# keyboard.net
KiCad netlist of a schematic drawn in EAGLE
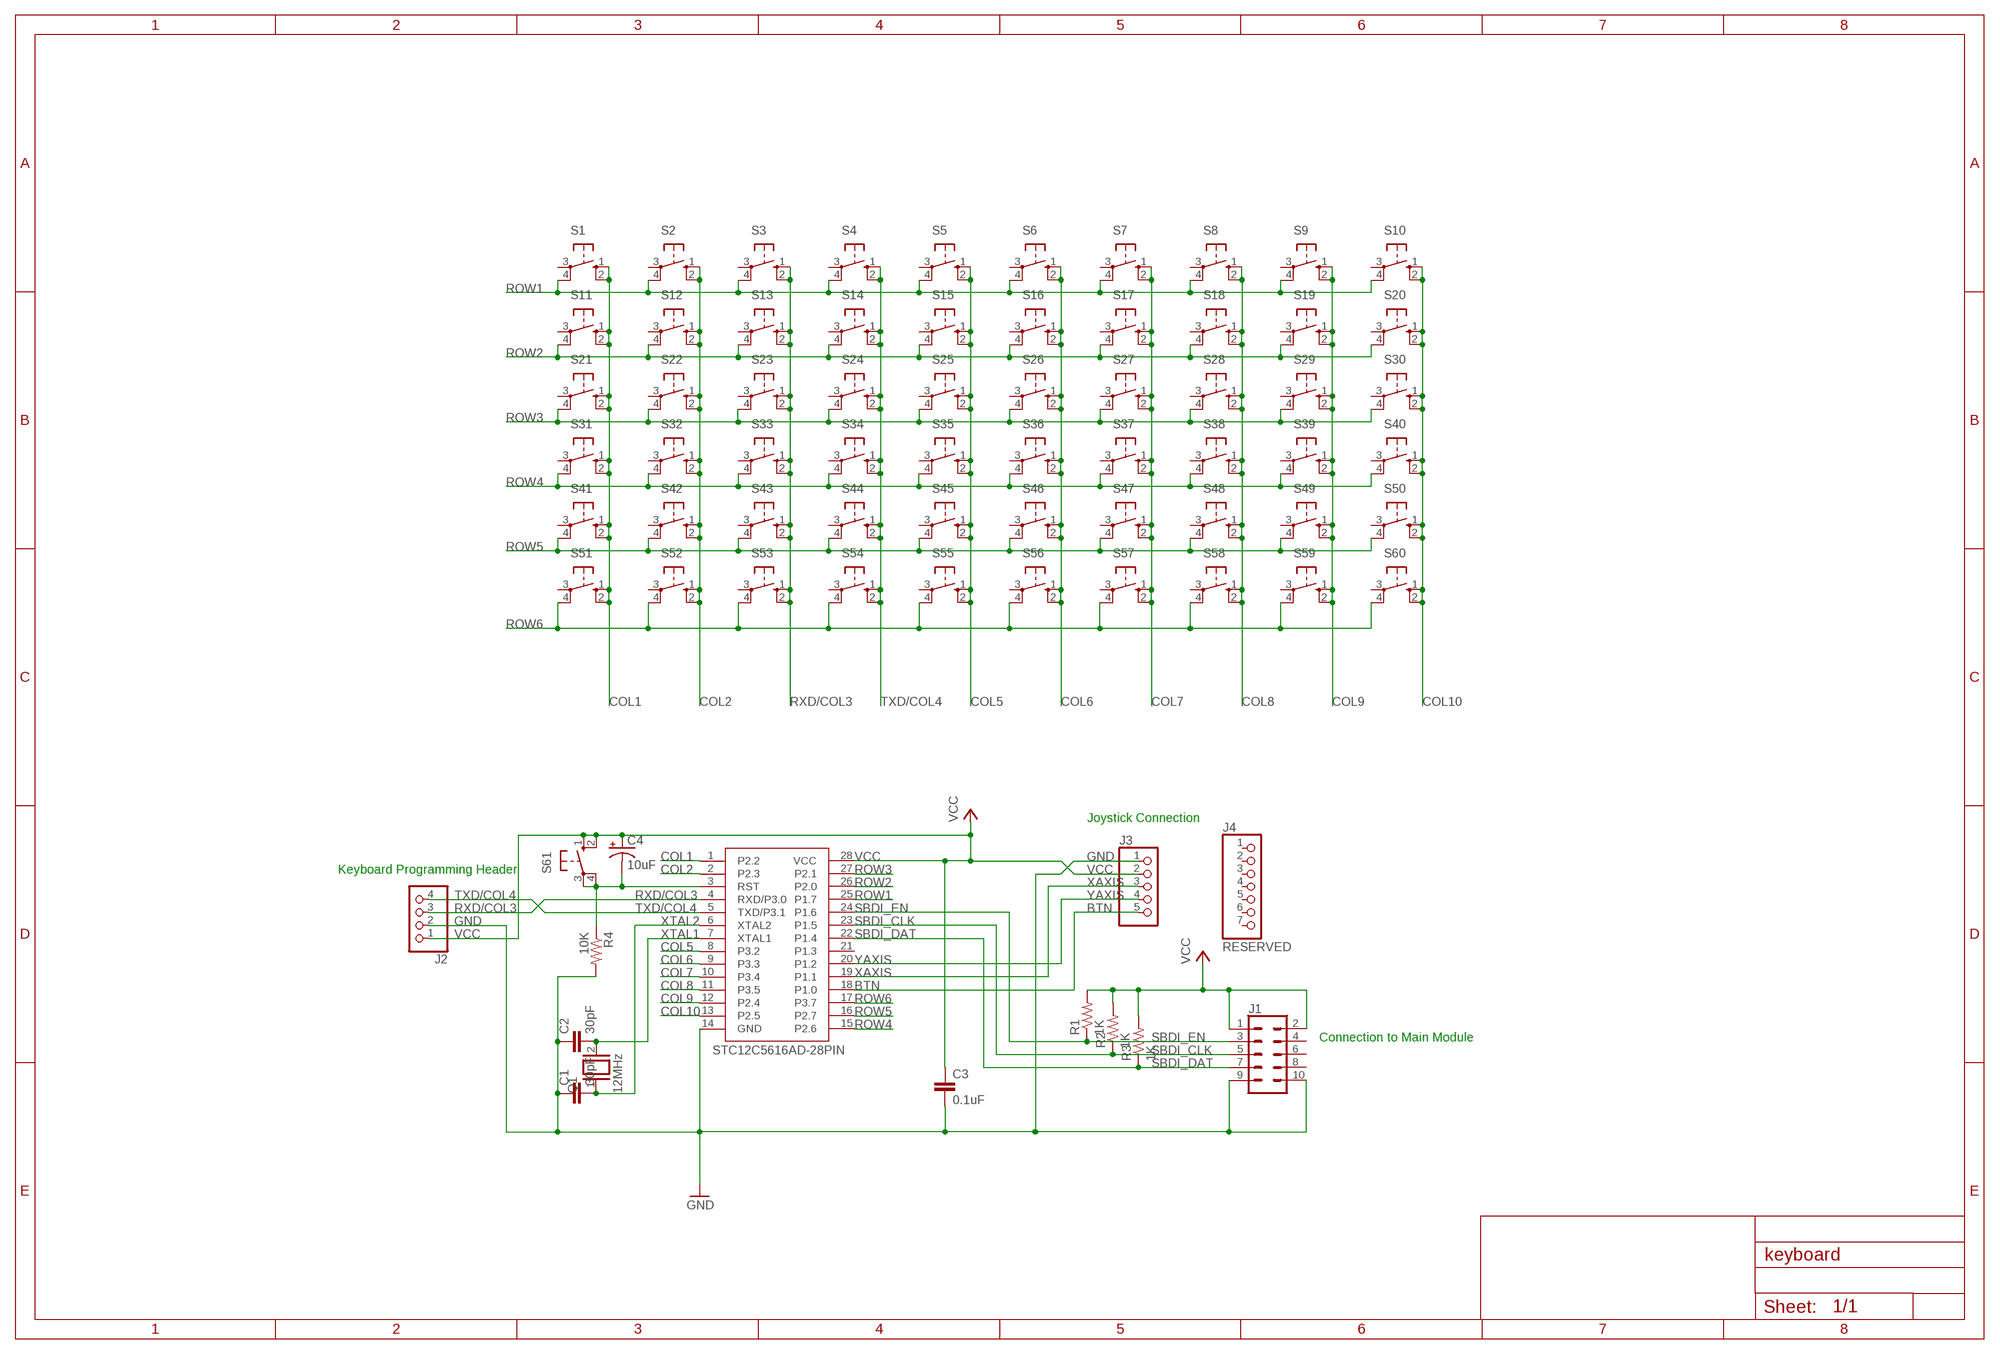
[diagram p0: schematic, sheet 1]

(export (version "E")
  (design (tool "Eeschema 10.0.6"))
  (components
    (comp (ref "C1")
      (value "30pF")
      (footprint "eagle-import:C025-025X050")
      (libsource (lib "eagle-import") (part "C-EU025-025X050"))
    )
    (comp (ref "C2")
      (value "30pF")
      (footprint "eagle-import:C025-025X050")
      (libsource (lib "eagle-import") (part "C-EU025-025X050"))
    )
    (comp (ref "C3")
      (value "0.1uF")
      (footprint "eagle-import:C025-030X050")
      (libsource (lib "eagle-import") (part "C-EU025-030X050"))
    )
    (comp (ref "C4")
      (value "10uF")
      (footprint "eagle-import:E1,8-4")
      (libsource (lib "eagle-import") (part "CPOL-USE1.8-4"))
    )
    (comp (ref "IC1")
      (value "STC12C5616AD")
      (footprint "eagle-import:DIP787W45P254L3505H508Q28B")
      (libsource (lib "eagle-import") (part "STC12C5616AD-28PIN"))
    )
    (comp (ref "J1")
      (value "CONN_05X2SHD_LOCK")
      (footprint "eagle-import:2X5-SHROUDED_LOCK")
      (libsource (lib "eagle-import") (part "CONN_05X2SHD_LOCK"))
    )
    (comp (ref "J2")
      (value "PINHD-1X4")
      (footprint "eagle-import:1X04")
      (libsource (lib "eagle-import") (part "PINHD-1X4"))
    )
    (comp (ref "J3")
      (value "PINHD-1X5")
      (footprint "eagle-import:1X05")
      (libsource (lib "eagle-import") (part "PINHD-1X5"))
    )
    (comp (ref "J4")
      (value "RESERVED")
      (footprint "eagle-import:1X07")
      (libsource (lib "eagle-import") (part "PINHD-1X7"))
    )
    (comp (ref "Q1")
      (value "12MHz")
      (footprint "eagle-import:QS")
      (libsource (lib "eagle-import") (part "XTAL/S"))
    )
    (comp (ref "R1")
      (value "1K")
      (footprint "eagle-import:0204_7")
      (libsource (lib "eagle-import") (part "R-US_0204/7"))
    )
    (comp (ref "R2")
      (value "1K")
      (footprint "eagle-import:0204_7")
      (libsource (lib "eagle-import") (part "R-US_0204/7"))
    )
    (comp (ref "R3")
      (value "1K")
      (footprint "eagle-import:0204_7")
      (libsource (lib "eagle-import") (part "R-US_0204/7"))
    )
    (comp (ref "R4")
      (value "10K")
      (footprint "eagle-import:0204_7")
      (libsource (lib "eagle-import") (part "R-US_0204/7"))
    )
    (comp (ref "S1")
      (value "10-XX")
      (footprint "eagle-import:B3F-10XX")
      (fields (field (name "MPN") "B3F-1000"))
      (libsource (lib "eagle-import") (part "10-XX"))
    )
    (comp (ref "S2")
      (value "10-XX")
      (footprint "eagle-import:B3F-10XX")
      (fields (field (name "MPN") "B3F-1000"))
      (libsource (lib "eagle-import") (part "10-XX"))
    )
    (comp (ref "S3")
      (value "10-XX")
      (footprint "eagle-import:B3F-10XX")
      (fields (field (name "MPN") "B3F-1000"))
      (libsource (lib "eagle-import") (part "10-XX"))
    )
    (comp (ref "S4")
      (value "10-XX")
      (footprint "eagle-import:B3F-10XX")
      (fields (field (name "MPN") "B3F-1000"))
      (libsource (lib "eagle-import") (part "10-XX"))
    )
    (comp (ref "S5")
      (value "10-XX")
      (footprint "eagle-import:B3F-10XX")
      (fields (field (name "MPN") "B3F-1000"))
      (libsource (lib "eagle-import") (part "10-XX"))
    )
    (comp (ref "S6")
      (value "10-XX")
      (footprint "eagle-import:B3F-10XX")
      (fields (field (name "MPN") "B3F-1000"))
      (libsource (lib "eagle-import") (part "10-XX"))
    )
    (comp (ref "S7")
      (value "10-XX")
      (footprint "eagle-import:B3F-10XX")
      (fields (field (name "MPN") "B3F-1000"))
      (libsource (lib "eagle-import") (part "10-XX"))
    )
    (comp (ref "S8")
      (value "10-XX")
      (footprint "eagle-import:B3F-10XX")
      (fields (field (name "MPN") "B3F-1000"))
      (libsource (lib "eagle-import") (part "10-XX"))
    )
    (comp (ref "S9")
      (value "10-XX")
      (footprint "eagle-import:B3F-10XX")
      (fields (field (name "MPN") "B3F-1000"))
      (libsource (lib "eagle-import") (part "10-XX"))
    )
    (comp (ref "S10")
      (value "10-XX")
      (footprint "eagle-import:B3F-10XX")
      (fields (field (name "MPN") "B3F-1000"))
      (libsource (lib "eagle-import") (part "10-XX"))
    )
    (comp (ref "S11")
      (value "10-XX")
      (footprint "eagle-import:B3F-10XX")
      (fields (field (name "MPN") "B3F-1000"))
      (libsource (lib "eagle-import") (part "10-XX"))
    )
    (comp (ref "S12")
      (value "10-XX")
      (footprint "eagle-import:B3F-10XX")
      (fields (field (name "MPN") "B3F-1000"))
      (libsource (lib "eagle-import") (part "10-XX"))
    )
    (comp (ref "S13")
      (value "10-XX")
      (footprint "eagle-import:B3F-10XX")
      (fields (field (name "MPN") "B3F-1000"))
      (libsource (lib "eagle-import") (part "10-XX"))
    )
    (comp (ref "S14")
      (value "10-XX")
      (footprint "eagle-import:B3F-10XX")
      (fields (field (name "MPN") "B3F-1000"))
      (libsource (lib "eagle-import") (part "10-XX"))
    )
    (comp (ref "S15")
      (value "10-XX")
      (footprint "eagle-import:B3F-10XX")
      (fields (field (name "MPN") "B3F-1000"))
      (libsource (lib "eagle-import") (part "10-XX"))
    )
    (comp (ref "S16")
      (value "10-XX")
      (footprint "eagle-import:B3F-10XX")
      (fields (field (name "MPN") "B3F-1000"))
      (libsource (lib "eagle-import") (part "10-XX"))
    )
    (comp (ref "S17")
      (value "10-XX")
      (footprint "eagle-import:B3F-10XX")
      (fields (field (name "MPN") "B3F-1000"))
      (libsource (lib "eagle-import") (part "10-XX"))
    )
    (comp (ref "S18")
      (value "10-XX")
      (footprint "eagle-import:B3F-10XX")
      (fields (field (name "MPN") "B3F-1000"))
      (libsource (lib "eagle-import") (part "10-XX"))
    )
    (comp (ref "S19")
      (value "10-XX")
      (footprint "eagle-import:B3F-10XX")
      (fields (field (name "MPN") "B3F-1000"))
      (libsource (lib "eagle-import") (part "10-XX"))
    )
    (comp (ref "S20")
      (value "10-XX")
      (footprint "eagle-import:B3F-10XX")
      (fields (field (name "MPN") "B3F-1000"))
      (libsource (lib "eagle-import") (part "10-XX"))
    )
    (comp (ref "S21")
      (value "10-XX")
      (footprint "eagle-import:B3F-10XX")
      (fields (field (name "MPN") "B3F-1000"))
      (libsource (lib "eagle-import") (part "10-XX"))
    )
    (comp (ref "S22")
      (value "10-XX")
      (footprint "eagle-import:B3F-10XX")
      (fields (field (name "MPN") "B3F-1000"))
      (libsource (lib "eagle-import") (part "10-XX"))
    )
    (comp (ref "S23")
      (value "10-XX")
      (footprint "eagle-import:B3F-10XX")
      (fields (field (name "MPN") "B3F-1000"))
      (libsource (lib "eagle-import") (part "10-XX"))
    )
    (comp (ref "S24")
      (value "10-XX")
      (footprint "eagle-import:B3F-10XX")
      (fields (field (name "MPN") "B3F-1000"))
      (libsource (lib "eagle-import") (part "10-XX"))
    )
    (comp (ref "S25")
      (value "10-XX")
      (footprint "eagle-import:B3F-10XX")
      (fields (field (name "MPN") "B3F-1000"))
      (libsource (lib "eagle-import") (part "10-XX"))
    )
    (comp (ref "S26")
      (value "10-XX")
      (footprint "eagle-import:B3F-10XX")
      (fields (field (name "MPN") "B3F-1000"))
      (libsource (lib "eagle-import") (part "10-XX"))
    )
    (comp (ref "S27")
      (value "10-XX")
      (footprint "eagle-import:B3F-10XX")
      (fields (field (name "MPN") "B3F-1000"))
      (libsource (lib "eagle-import") (part "10-XX"))
    )
    (comp (ref "S28")
      (value "10-XX")
      (footprint "eagle-import:B3F-10XX")
      (fields (field (name "MPN") "B3F-1000"))
      (libsource (lib "eagle-import") (part "10-XX"))
    )
    (comp (ref "S29")
      (value "10-XX")
      (footprint "eagle-import:B3F-10XX")
      (fields (field (name "MPN") "B3F-1000"))
      (libsource (lib "eagle-import") (part "10-XX"))
    )
    (comp (ref "S30")
      (value "10-XX")
      (footprint "eagle-import:B3F-10XX")
      (fields (field (name "MPN") "B3F-1000"))
      (libsource (lib "eagle-import") (part "10-XX"))
    )
    (comp (ref "S31")
      (value "10-XX")
      (footprint "eagle-import:B3F-10XX")
      (fields (field (name "MPN") "B3F-1000"))
      (libsource (lib "eagle-import") (part "10-XX"))
    )
    (comp (ref "S32")
      (value "10-XX")
      (footprint "eagle-import:B3F-10XX")
      (fields (field (name "MPN") "B3F-1000"))
      (libsource (lib "eagle-import") (part "10-XX"))
    )
    (comp (ref "S33")
      (value "10-XX")
      (footprint "eagle-import:B3F-10XX")
      (fields (field (name "MPN") "B3F-1000"))
      (libsource (lib "eagle-import") (part "10-XX"))
    )
    (comp (ref "S34")
      (value "10-XX")
      (footprint "eagle-import:B3F-10XX")
      (fields (field (name "MPN") "B3F-1000"))
      (libsource (lib "eagle-import") (part "10-XX"))
    )
    (comp (ref "S35")
      (value "10-XX")
      (footprint "eagle-import:B3F-10XX")
      (fields (field (name "MPN") "B3F-1000"))
      (libsource (lib "eagle-import") (part "10-XX"))
    )
    (comp (ref "S36")
      (value "10-XX")
      (footprint "eagle-import:B3F-10XX")
      (fields (field (name "MPN") "B3F-1000"))
      (libsource (lib "eagle-import") (part "10-XX"))
    )
    (comp (ref "S37")
      (value "10-XX")
      (footprint "eagle-import:B3F-10XX")
      (fields (field (name "MPN") "B3F-1000"))
      (libsource (lib "eagle-import") (part "10-XX"))
    )
    (comp (ref "S38")
      (value "10-XX")
      (footprint "eagle-import:B3F-10XX")
      (fields (field (name "MPN") "B3F-1000"))
      (libsource (lib "eagle-import") (part "10-XX"))
    )
    (comp (ref "S39")
      (value "10-XX")
      (footprint "eagle-import:B3F-10XX")
      (fields (field (name "MPN") "B3F-1000"))
      (libsource (lib "eagle-import") (part "10-XX"))
    )
    (comp (ref "S40")
      (value "10-XX")
      (footprint "eagle-import:B3F-10XX")
      (fields (field (name "MPN") "B3F-1000"))
      (libsource (lib "eagle-import") (part "10-XX"))
    )
    (comp (ref "S41")
      (value "10-XX")
      (footprint "eagle-import:B3F-10XX")
      (fields (field (name "MPN") "B3F-1000"))
      (libsource (lib "eagle-import") (part "10-XX"))
    )
    (comp (ref "S42")
      (value "10-XX")
      (footprint "eagle-import:B3F-10XX")
      (fields (field (name "MPN") "B3F-1000"))
      (libsource (lib "eagle-import") (part "10-XX"))
    )
    (comp (ref "S43")
      (value "10-XX")
      (footprint "eagle-import:B3F-10XX")
      (fields (field (name "MPN") "B3F-1000"))
      (libsource (lib "eagle-import") (part "10-XX"))
    )
    (comp (ref "S44")
      (value "10-XX")
      (footprint "eagle-import:B3F-10XX")
      (fields (field (name "MPN") "B3F-1000"))
      (libsource (lib "eagle-import") (part "10-XX"))
    )
    (comp (ref "S45")
      (value "10-XX")
      (footprint "eagle-import:B3F-10XX")
      (fields (field (name "MPN") "B3F-1000"))
      (libsource (lib "eagle-import") (part "10-XX"))
    )
    (comp (ref "S46")
      (value "10-XX")
      (footprint "eagle-import:B3F-10XX")
      (fields (field (name "MPN") "B3F-1000"))
      (libsource (lib "eagle-import") (part "10-XX"))
    )
    (comp (ref "S47")
      (value "10-XX")
      (footprint "eagle-import:B3F-10XX")
      (fields (field (name "MPN") "B3F-1000"))
      (libsource (lib "eagle-import") (part "10-XX"))
    )
    (comp (ref "S48")
      (value "10-XX")
      (footprint "eagle-import:B3F-10XX")
      (fields (field (name "MPN") "B3F-1000"))
      (libsource (lib "eagle-import") (part "10-XX"))
    )
    (comp (ref "S49")
      (value "10-XX")
      (footprint "eagle-import:B3F-10XX")
      (fields (field (name "MPN") "B3F-1000"))
      (libsource (lib "eagle-import") (part "10-XX"))
    )
    (comp (ref "S50")
      (value "10-XX")
      (footprint "eagle-import:B3F-10XX")
      (fields (field (name "MPN") "B3F-1000"))
      (libsource (lib "eagle-import") (part "10-XX"))
    )
    (comp (ref "S51")
      (value "10-XX")
      (footprint "eagle-import:B3F-10XX")
      (fields (field (name "MPN") "B3F-1000"))
      (libsource (lib "eagle-import") (part "10-XX"))
    )
    (comp (ref "S52")
      (value "10-XX")
      (footprint "eagle-import:B3F-10XX")
      (fields (field (name "MPN") "B3F-1000"))
      (libsource (lib "eagle-import") (part "10-XX"))
    )
    (comp (ref "S53")
      (value "10-XX")
      (footprint "eagle-import:B3F-10XX")
      (fields (field (name "MPN") "B3F-1000"))
      (libsource (lib "eagle-import") (part "10-XX"))
    )
    (comp (ref "S54")
      (value "10-XX")
      (footprint "eagle-import:B3F-10XX")
      (fields (field (name "MPN") "B3F-1000"))
      (libsource (lib "eagle-import") (part "10-XX"))
    )
    (comp (ref "S55")
      (value "10-XX")
      (footprint "eagle-import:B3F-10XX")
      (fields (field (name "MPN") "B3F-1000"))
      (libsource (lib "eagle-import") (part "10-XX"))
    )
    (comp (ref "S56")
      (value "10-XX")
      (footprint "eagle-import:B3F-10XX")
      (fields (field (name "MPN") "B3F-1000"))
      (libsource (lib "eagle-import") (part "10-XX"))
    )
    (comp (ref "S57")
      (value "10-XX")
      (footprint "eagle-import:B3F-10XX")
      (fields (field (name "MPN") "B3F-1000"))
      (libsource (lib "eagle-import") (part "10-XX"))
    )
    (comp (ref "S58")
      (value "10-XX")
      (footprint "eagle-import:B3F-10XX")
      (fields (field (name "MPN") "B3F-1000"))
      (libsource (lib "eagle-import") (part "10-XX"))
    )
    (comp (ref "S59")
      (value "10-XX")
      (footprint "eagle-import:B3F-10XX")
      (fields (field (name "MPN") "B3F-1000"))
      (libsource (lib "eagle-import") (part "10-XX"))
    )
    (comp (ref "S60")
      (value "10-XX")
      (footprint "eagle-import:B3F-10XX")
      (fields (field (name "MPN") "B3F-1000"))
      (libsource (lib "eagle-import") (part "10-XX"))
    )
    (comp (ref "S61")
      (value "10-XX")
      (footprint "eagle-import:B3F-10XX")
      (fields (field (name "MPN") "B3F-1000"))
      (libsource (lib "eagle-import") (part "10-XX"))
    )
  )
  (nets
    (net (code "1") (name "/BTN") (class "Default")
      (node (ref "IC1") (pin "18") (pinfunction "P1.0_18") (pintype "bidirectional"))
      (node (ref "J3") (pin "5") (pinfunction "5_5") (pintype "passive"))
    )
    (net (code "2") (name "/COL1") (class "Default")
      (node (ref "IC1") (pin "1") (pinfunction "P2.2_1") (pintype "bidirectional"))
      (node (ref "S1") (pin "1") (pinfunction "S_1") (pintype "passive"))
      (node (ref "S1") (pin "2") (pinfunction "S1_2") (pintype "passive"))
      (node (ref "S11") (pin "1") (pinfunction "S_1") (pintype "passive"))
      (node (ref "S11") (pin "2") (pinfunction "S1_2") (pintype "passive"))
      (node (ref "S21") (pin "1") (pinfunction "S_1") (pintype "passive"))
      (node (ref "S21") (pin "2") (pinfunction "S1_2") (pintype "passive"))
      (node (ref "S31") (pin "1") (pinfunction "S_1") (pintype "passive"))
      (node (ref "S31") (pin "2") (pinfunction "S1_2") (pintype "passive"))
      (node (ref "S41") (pin "1") (pinfunction "S_1") (pintype "passive"))
      (node (ref "S41") (pin "2") (pinfunction "S1_2") (pintype "passive"))
      (node (ref "S51") (pin "1") (pinfunction "S_1") (pintype "passive"))
      (node (ref "S51") (pin "2") (pinfunction "S1_2") (pintype "passive"))
    )
    (net (code "3") (name "/COL2") (class "Default")
      (node (ref "IC1") (pin "2") (pinfunction "P2.3_2") (pintype "bidirectional"))
      (node (ref "S12") (pin "1") (pinfunction "S_1") (pintype "passive"))
      (node (ref "S12") (pin "2") (pinfunction "S1_2") (pintype "passive"))
      (node (ref "S2") (pin "1") (pinfunction "S_1") (pintype "passive"))
      (node (ref "S2") (pin "2") (pinfunction "S1_2") (pintype "passive"))
      (node (ref "S22") (pin "1") (pinfunction "S_1") (pintype "passive"))
      (node (ref "S22") (pin "2") (pinfunction "S1_2") (pintype "passive"))
      (node (ref "S32") (pin "1") (pinfunction "S_1") (pintype "passive"))
      (node (ref "S32") (pin "2") (pinfunction "S1_2") (pintype "passive"))
      (node (ref "S42") (pin "1") (pinfunction "S_1") (pintype "passive"))
      (node (ref "S42") (pin "2") (pinfunction "S1_2") (pintype "passive"))
      (node (ref "S52") (pin "1") (pinfunction "S_1") (pintype "passive"))
      (node (ref "S52") (pin "2") (pinfunction "S1_2") (pintype "passive"))
    )
    (net (code "4") (name "/COL5") (class "Default")
      (node (ref "IC1") (pin "8") (pinfunction "P3.2_8") (pintype "bidirectional"))
      (node (ref "S15") (pin "1") (pinfunction "S_1") (pintype "passive"))
      (node (ref "S15") (pin "2") (pinfunction "S1_2") (pintype "passive"))
      (node (ref "S25") (pin "1") (pinfunction "S_1") (pintype "passive"))
      (node (ref "S25") (pin "2") (pinfunction "S1_2") (pintype "passive"))
      (node (ref "S35") (pin "1") (pinfunction "S_1") (pintype "passive"))
      (node (ref "S35") (pin "2") (pinfunction "S1_2") (pintype "passive"))
      (node (ref "S45") (pin "1") (pinfunction "S_1") (pintype "passive"))
      (node (ref "S45") (pin "2") (pinfunction "S1_2") (pintype "passive"))
      (node (ref "S5") (pin "1") (pinfunction "S_1") (pintype "passive"))
      (node (ref "S5") (pin "2") (pinfunction "S1_2") (pintype "passive"))
      (node (ref "S55") (pin "1") (pinfunction "S_1") (pintype "passive"))
      (node (ref "S55") (pin "2") (pinfunction "S1_2") (pintype "passive"))
    )
    (net (code "5") (name "/COL6") (class "Default")
      (node (ref "IC1") (pin "9") (pinfunction "P3.3_9") (pintype "bidirectional"))
      (node (ref "S16") (pin "1") (pinfunction "S_1") (pintype "passive"))
      (node (ref "S16") (pin "2") (pinfunction "S1_2") (pintype "passive"))
      (node (ref "S26") (pin "1") (pinfunction "S_1") (pintype "passive"))
      (node (ref "S26") (pin "2") (pinfunction "S1_2") (pintype "passive"))
      (node (ref "S36") (pin "1") (pinfunction "S_1") (pintype "passive"))
      (node (ref "S36") (pin "2") (pinfunction "S1_2") (pintype "passive"))
      (node (ref "S46") (pin "1") (pinfunction "S_1") (pintype "passive"))
      (node (ref "S46") (pin "2") (pinfunction "S1_2") (pintype "passive"))
      (node (ref "S56") (pin "1") (pinfunction "S_1") (pintype "passive"))
      (node (ref "S56") (pin "2") (pinfunction "S1_2") (pintype "passive"))
      (node (ref "S6") (pin "1") (pinfunction "S_1") (pintype "passive"))
      (node (ref "S6") (pin "2") (pinfunction "S1_2") (pintype "passive"))
    )
    (net (code "6") (name "/COL7") (class "Default")
      (node (ref "IC1") (pin "10") (pinfunction "P3.4_10") (pintype "bidirectional"))
      (node (ref "S17") (pin "1") (pinfunction "S_1") (pintype "passive"))
      (node (ref "S17") (pin "2") (pinfunction "S1_2") (pintype "passive"))
      (node (ref "S27") (pin "1") (pinfunction "S_1") (pintype "passive"))
      (node (ref "S27") (pin "2") (pinfunction "S1_2") (pintype "passive"))
      (node (ref "S37") (pin "1") (pinfunction "S_1") (pintype "passive"))
      (node (ref "S37") (pin "2") (pinfunction "S1_2") (pintype "passive"))
      (node (ref "S47") (pin "1") (pinfunction "S_1") (pintype "passive"))
      (node (ref "S47") (pin "2") (pinfunction "S1_2") (pintype "passive"))
      (node (ref "S57") (pin "1") (pinfunction "S_1") (pintype "passive"))
      (node (ref "S57") (pin "2") (pinfunction "S1_2") (pintype "passive"))
      (node (ref "S7") (pin "1") (pinfunction "S_1") (pintype "passive"))
      (node (ref "S7") (pin "2") (pinfunction "S1_2") (pintype "passive"))
    )
    (net (code "7") (name "/COL8") (class "Default")
      (node (ref "IC1") (pin "11") (pinfunction "P3.5_11") (pintype "bidirectional"))
      (node (ref "S18") (pin "1") (pinfunction "S_1") (pintype "passive"))
      (node (ref "S18") (pin "2") (pinfunction "S1_2") (pintype "passive"))
      (node (ref "S28") (pin "1") (pinfunction "S_1") (pintype "passive"))
      (node (ref "S28") (pin "2") (pinfunction "S1_2") (pintype "passive"))
      (node (ref "S38") (pin "1") (pinfunction "S_1") (pintype "passive"))
      (node (ref "S38") (pin "2") (pinfunction "S1_2") (pintype "passive"))
      (node (ref "S48") (pin "1") (pinfunction "S_1") (pintype "passive"))
      (node (ref "S48") (pin "2") (pinfunction "S1_2") (pintype "passive"))
      (node (ref "S58") (pin "1") (pinfunction "S_1") (pintype "passive"))
      (node (ref "S58") (pin "2") (pinfunction "S1_2") (pintype "passive"))
      (node (ref "S8") (pin "1") (pinfunction "S_1") (pintype "passive"))
      (node (ref "S8") (pin "2") (pinfunction "S1_2") (pintype "passive"))
    )
    (net (code "8") (name "/COL9") (class "Default")
      (node (ref "IC1") (pin "12") (pinfunction "P2.4_12") (pintype "bidirectional"))
      (node (ref "S19") (pin "1") (pinfunction "S_1") (pintype "passive"))
      (node (ref "S19") (pin "2") (pinfunction "S1_2") (pintype "passive"))
      (node (ref "S29") (pin "1") (pinfunction "S_1") (pintype "passive"))
      (node (ref "S29") (pin "2") (pinfunction "S1_2") (pintype "passive"))
      (node (ref "S39") (pin "1") (pinfunction "S_1") (pintype "passive"))
      (node (ref "S39") (pin "2") (pinfunction "S1_2") (pintype "passive"))
      (node (ref "S49") (pin "1") (pinfunction "S_1") (pintype "passive"))
      (node (ref "S49") (pin "2") (pinfunction "S1_2") (pintype "passive"))
      (node (ref "S59") (pin "1") (pinfunction "S_1") (pintype "passive"))
      (node (ref "S59") (pin "2") (pinfunction "S1_2") (pintype "passive"))
      (node (ref "S9") (pin "1") (pinfunction "S_1") (pintype "passive"))
      (node (ref "S9") (pin "2") (pinfunction "S1_2") (pintype "passive"))
    )
    (net (code "9") (name "/COL10") (class "Default")
      (node (ref "IC1") (pin "13") (pinfunction "P2.5_13") (pintype "bidirectional"))
      (node (ref "S10") (pin "1") (pinfunction "S_1") (pintype "passive"))
      (node (ref "S10") (pin "2") (pinfunction "S1_2") (pintype "passive"))
      (node (ref "S20") (pin "1") (pinfunction "S_1") (pintype "passive"))
      (node (ref "S20") (pin "2") (pinfunction "S1_2") (pintype "passive"))
      (node (ref "S30") (pin "1") (pinfunction "S_1") (pintype "passive"))
      (node (ref "S30") (pin "2") (pinfunction "S1_2") (pintype "passive"))
      (node (ref "S40") (pin "1") (pinfunction "S_1") (pintype "passive"))
      (node (ref "S40") (pin "2") (pinfunction "S1_2") (pintype "passive"))
      (node (ref "S50") (pin "1") (pinfunction "S_1") (pintype "passive"))
      (node (ref "S50") (pin "2") (pinfunction "S1_2") (pintype "passive"))
      (node (ref "S60") (pin "1") (pinfunction "S_1") (pintype "passive"))
      (node (ref "S60") (pin "2") (pinfunction "S1_2") (pintype "passive"))
    )
    (net (code "10") (name "/ROW1") (class "Default")
      (node (ref "IC1") (pin "25") (pinfunction "P1.7_25") (pintype "bidirectional"))
      (node (ref "S1") (pin "4") (pinfunction "P1_4") (pintype "passive"))
      (node (ref "S10") (pin "4") (pinfunction "P1_4") (pintype "passive"))
      (node (ref "S2") (pin "4") (pinfunction "P1_4") (pintype "passive"))
      (node (ref "S3") (pin "4") (pinfunction "P1_4") (pintype "passive"))
      (node (ref "S4") (pin "4") (pinfunction "P1_4") (pintype "passive"))
      (node (ref "S5") (pin "4") (pinfunction "P1_4") (pintype "passive"))
      (node (ref "S6") (pin "4") (pinfunction "P1_4") (pintype "passive"))
      (node (ref "S7") (pin "4") (pinfunction "P1_4") (pintype "passive"))
      (node (ref "S8") (pin "4") (pinfunction "P1_4") (pintype "passive"))
      (node (ref "S9") (pin "4") (pinfunction "P1_4") (pintype "passive"))
    )
    (net (code "11") (name "/ROW2") (class "Default")
      (node (ref "IC1") (pin "26") (pinfunction "P2.0_26") (pintype "bidirectional"))
      (node (ref "S11") (pin "4") (pinfunction "P1_4") (pintype "passive"))
      (node (ref "S12") (pin "4") (pinfunction "P1_4") (pintype "passive"))
      (node (ref "S13") (pin "4") (pinfunction "P1_4") (pintype "passive"))
      (node (ref "S14") (pin "4") (pinfunction "P1_4") (pintype "passive"))
      (node (ref "S15") (pin "4") (pinfunction "P1_4") (pintype "passive"))
      (node (ref "S16") (pin "4") (pinfunction "P1_4") (pintype "passive"))
      (node (ref "S17") (pin "4") (pinfunction "P1_4") (pintype "passive"))
      (node (ref "S18") (pin "4") (pinfunction "P1_4") (pintype "passive"))
      (node (ref "S19") (pin "4") (pinfunction "P1_4") (pintype "passive"))
      (node (ref "S20") (pin "4") (pinfunction "P1_4") (pintype "passive"))
    )
    (net (code "12") (name "/ROW3") (class "Default")
      (node (ref "IC1") (pin "27") (pinfunction "P2.1_27") (pintype "bidirectional"))
      (node (ref "S21") (pin "4") (pinfunction "P1_4") (pintype "passive"))
      (node (ref "S22") (pin "4") (pinfunction "P1_4") (pintype "passive"))
      (node (ref "S23") (pin "4") (pinfunction "P1_4") (pintype "passive"))
      (node (ref "S24") (pin "4") (pinfunction "P1_4") (pintype "passive"))
      (node (ref "S25") (pin "4") (pinfunction "P1_4") (pintype "passive"))
      (node (ref "S26") (pin "4") (pinfunction "P1_4") (pintype "passive"))
      (node (ref "S27") (pin "4") (pinfunction "P1_4") (pintype "passive"))
      (node (ref "S28") (pin "4") (pinfunction "P1_4") (pintype "passive"))
      (node (ref "S29") (pin "4") (pinfunction "P1_4") (pintype "passive"))
      (node (ref "S30") (pin "4") (pinfunction "P1_4") (pintype "passive"))
    )
    (net (code "13") (name "/ROW4") (class "Default")
      (node (ref "IC1") (pin "15") (pinfunction "P2.6_15") (pintype "bidirectional"))
      (node (ref "S31") (pin "4") (pinfunction "P1_4") (pintype "passive"))
      (node (ref "S32") (pin "4") (pinfunction "P1_4") (pintype "passive"))
      (node (ref "S33") (pin "4") (pinfunction "P1_4") (pintype "passive"))
      (node (ref "S34") (pin "4") (pinfunction "P1_4") (pintype "passive"))
      (node (ref "S35") (pin "4") (pinfunction "P1_4") (pintype "passive"))
      (node (ref "S36") (pin "4") (pinfunction "P1_4") (pintype "passive"))
      (node (ref "S37") (pin "4") (pinfunction "P1_4") (pintype "passive"))
      (node (ref "S38") (pin "4") (pinfunction "P1_4") (pintype "passive"))
      (node (ref "S39") (pin "4") (pinfunction "P1_4") (pintype "passive"))
      (node (ref "S40") (pin "4") (pinfunction "P1_4") (pintype "passive"))
    )
    (net (code "14") (name "/ROW5") (class "Default")
      (node (ref "IC1") (pin "16") (pinfunction "P2.7_16") (pintype "bidirectional"))
      (node (ref "S41") (pin "4") (pinfunction "P1_4") (pintype "passive"))
      (node (ref "S42") (pin "4") (pinfunction "P1_4") (pintype "passive"))
      (node (ref "S43") (pin "4") (pinfunction "P1_4") (pintype "passive"))
      (node (ref "S44") (pin "4") (pinfunction "P1_4") (pintype "passive"))
      (node (ref "S45") (pin "4") (pinfunction "P1_4") (pintype "passive"))
      (node (ref "S46") (pin "4") (pinfunction "P1_4") (pintype "passive"))
      (node (ref "S47") (pin "4") (pinfunction "P1_4") (pintype "passive"))
      (node (ref "S48") (pin "4") (pinfunction "P1_4") (pintype "passive"))
      (node (ref "S49") (pin "4") (pinfunction "P1_4") (pintype "passive"))
      (node (ref "S50") (pin "4") (pinfunction "P1_4") (pintype "passive"))
    )
    (net (code "15") (name "/ROW6") (class "Default")
      (node (ref "IC1") (pin "17") (pinfunction "P3.7_17") (pintype "bidirectional"))
      (node (ref "S51") (pin "4") (pinfunction "P1_4") (pintype "passive"))
      (node (ref "S52") (pin "4") (pinfunction "P1_4") (pintype "passive"))
      (node (ref "S53") (pin "4") (pinfunction "P1_4") (pintype "passive"))
      (node (ref "S54") (pin "4") (pinfunction "P1_4") (pintype "passive"))
      (node (ref "S55") (pin "4") (pinfunction "P1_4") (pintype "passive"))
      (node (ref "S56") (pin "4") (pinfunction "P1_4") (pintype "passive"))
      (node (ref "S57") (pin "4") (pinfunction "P1_4") (pintype "passive"))
      (node (ref "S58") (pin "4") (pinfunction "P1_4") (pintype "passive"))
      (node (ref "S59") (pin "4") (pinfunction "P1_4") (pintype "passive"))
      (node (ref "S60") (pin "4") (pinfunction "P1_4") (pintype "passive"))
    )
    (net (code "16") (name "/RXD{slash}COL3") (class "Default")
      (node (ref "IC1") (pin "4") (pinfunction "RXD/P3.0_4") (pintype "bidirectional"))
      (node (ref "J2") (pin "3") (pinfunction "3_3") (pintype "passive"))
      (node (ref "S13") (pin "1") (pinfunction "S_1") (pintype "passive"))
      (node (ref "S13") (pin "2") (pinfunction "S1_2") (pintype "passive"))
      (node (ref "S23") (pin "1") (pinfunction "S_1") (pintype "passive"))
      (node (ref "S23") (pin "2") (pinfunction "S1_2") (pintype "passive"))
      (node (ref "S3") (pin "1") (pinfunction "S_1") (pintype "passive"))
      (node (ref "S3") (pin "2") (pinfunction "S1_2") (pintype "passive"))
      (node (ref "S33") (pin "1") (pinfunction "S_1") (pintype "passive"))
      (node (ref "S33") (pin "2") (pinfunction "S1_2") (pintype "passive"))
      (node (ref "S43") (pin "1") (pinfunction "S_1") (pintype "passive"))
      (node (ref "S43") (pin "2") (pinfunction "S1_2") (pintype "passive"))
      (node (ref "S53") (pin "1") (pinfunction "S_1") (pintype "passive"))
      (node (ref "S53") (pin "2") (pinfunction "S1_2") (pintype "passive"))
    )
    (net (code "17") (name "/SBDI_CLK") (class "Default")
      (node (ref "IC1") (pin "23") (pinfunction "P1.5_23") (pintype "bidirectional"))
      (node (ref "J1") (pin "5") (pinfunction "5_5") (pintype "passive"))
      (node (ref "R2") (pin "1") (pinfunction "1_1") (pintype "passive"))
    )
    (net (code "18") (name "/SBDI_DAT") (class "Default")
      (node (ref "IC1") (pin "22") (pinfunction "P1.4_22") (pintype "bidirectional"))
      (node (ref "J1") (pin "7") (pinfunction "7_7") (pintype "passive"))
      (node (ref "R3") (pin "1") (pinfunction "1_1") (pintype "passive"))
    )
    (net (code "19") (name "/SBDI_EN") (class "Default")
      (node (ref "IC1") (pin "24") (pinfunction "P1.6_24") (pintype "bidirectional"))
      (node (ref "J1") (pin "3") (pinfunction "3_3") (pintype "passive"))
      (node (ref "R1") (pin "1") (pinfunction "1_1") (pintype "passive"))
    )
    (net (code "20") (name "/TXD{slash}COL4") (class "Default")
      (node (ref "IC1") (pin "5") (pinfunction "TXD/P3.1_5") (pintype "bidirectional"))
      (node (ref "J2") (pin "4") (pinfunction "4_4") (pintype "passive"))
      (node (ref "S14") (pin "1") (pinfunction "S_1") (pintype "passive"))
      (node (ref "S14") (pin "2") (pinfunction "S1_2") (pintype "passive"))
      (node (ref "S24") (pin "1") (pinfunction "S_1") (pintype "passive"))
      (node (ref "S24") (pin "2") (pinfunction "S1_2") (pintype "passive"))
      (node (ref "S34") (pin "1") (pinfunction "S_1") (pintype "passive"))
      (node (ref "S34") (pin "2") (pinfunction "S1_2") (pintype "passive"))
      (node (ref "S4") (pin "1") (pinfunction "S_1") (pintype "passive"))
      (node (ref "S4") (pin "2") (pinfunction "S1_2") (pintype "passive"))
      (node (ref "S44") (pin "1") (pinfunction "S_1") (pintype "passive"))
      (node (ref "S44") (pin "2") (pinfunction "S1_2") (pintype "passive"))
      (node (ref "S54") (pin "1") (pinfunction "S_1") (pintype "passive"))
      (node (ref "S54") (pin "2") (pinfunction "S1_2") (pintype "passive"))
    )
    (net (code "21") (name "/XAXIS") (class "Default")
      (node (ref "IC1") (pin "19") (pinfunction "P1.1_19") (pintype "bidirectional"))
      (node (ref "J3") (pin "3") (pinfunction "3_3") (pintype "passive"))
    )
    (net (code "22") (name "/XTAL1") (class "Default")
      (node (ref "C2") (pin "2") (pinfunction "2_2") (pintype "passive"))
      (node (ref "IC1") (pin "7") (pinfunction "XTAL1_7") (pintype "bidirectional"))
      (node (ref "Q1") (pin "2") (pinfunction "2_2") (pintype "passive"))
    )
    (net (code "23") (name "/XTAL2") (class "Default")
      (node (ref "C1") (pin "2") (pinfunction "2_2") (pintype "passive"))
      (node (ref "IC1") (pin "6") (pinfunction "XTAL2_6") (pintype "bidirectional"))
      (node (ref "Q1") (pin "1") (pinfunction "1_1") (pintype "passive"))
    )
    (net (code "24") (name "/YAXIS") (class "Default")
      (node (ref "IC1") (pin "20") (pinfunction "P1.2_20") (pintype "bidirectional"))
      (node (ref "J3") (pin "4") (pinfunction "4_4") (pintype "passive"))
    )
    (net (code "25") (name "GND") (class "Default")
      (node (ref "C1") (pin "1") (pinfunction "1_1") (pintype "passive"))
      (node (ref "C2") (pin "1") (pinfunction "1_1") (pintype "passive"))
      (node (ref "C3") (pin "2") (pinfunction "2_2") (pintype "passive"))
      (node (ref "IC1") (pin "14") (pinfunction "GND_14") (pintype "bidirectional"))
      (node (ref "J1") (pin "10") (pinfunction "10_10") (pintype "passive"))
      (node (ref "J1") (pin "9") (pinfunction "9_9") (pintype "passive"))
      (node (ref "J2") (pin "2") (pinfunction "2_2") (pintype "passive"))
      (node (ref "J3") (pin "1") (pinfunction "1_1") (pintype "passive"))
      (node (ref "R4") (pin "2") (pinfunction "2_2") (pintype "passive"))
    )
    (net (code "26") (name "Net-(IC1-RST)") (class "Default")
      (node (ref "C4") (pin "-") (pinfunction "-_-") (pintype "passive"))
      (node (ref "IC1") (pin "3") (pinfunction "RST_3") (pintype "bidirectional"))
      (node (ref "R4") (pin "1") (pinfunction "1_1") (pintype "passive"))
      (node (ref "S61") (pin "3") (pinfunction "P_3") (pintype "passive"))
      (node (ref "S61") (pin "4") (pinfunction "P1_4") (pintype "passive"))
    )
    (net (code "27") (name "VCC") (class "Default")
      (node (ref "C3") (pin "1") (pinfunction "1_1") (pintype "passive"))
      (node (ref "C4") (pin "+") (pinfunction "+_+") (pintype "passive"))
      (node (ref "IC1") (pin "28") (pinfunction "VCC_28") (pintype "bidirectional"))
      (node (ref "J1") (pin "1") (pinfunction "1_1") (pintype "passive"))
      (node (ref "J1") (pin "2") (pinfunction "2_2") (pintype "passive"))
      (node (ref "J2") (pin "1") (pinfunction "1_1") (pintype "passive"))
      (node (ref "J3") (pin "2") (pinfunction "2_2") (pintype "passive"))
      (node (ref "R1") (pin "2") (pinfunction "2_2") (pintype "passive"))
      (node (ref "R2") (pin "2") (pinfunction "2_2") (pintype "passive"))
      (node (ref "R3") (pin "2") (pinfunction "2_2") (pintype "passive"))
      (node (ref "S61") (pin "1") (pinfunction "S_1") (pintype "passive"))
      (node (ref "S61") (pin "2") (pinfunction "S1_2") (pintype "passive"))
    )
    (net (code "28") (name "unconnected-(IC1-P1.3-Pad21)") (class "Default")
      (node (ref "IC1") (pin "21") (pinfunction "P1.3_21") (pintype "bidirectional"))
    )
    (net (code "29") (name "unconnected-(J1-Pad4)") (class "Default")
      (node (ref "J1") (pin "4") (pinfunction "4_4") (pintype "passive"))
    )
    (net (code "30") (name "unconnected-(J1-Pad6)") (class "Default")
      (node (ref "J1") (pin "6") (pinfunction "6_6") (pintype "passive"))
    )
    (net (code "31") (name "unconnected-(J1-Pad8)") (class "Default")
      (node (ref "J1") (pin "8") (pinfunction "8_8") (pintype "passive"))
    )
    (net (code "32") (name "unconnected-(J4-Pad1)") (class "Default")
      (node (ref "J4") (pin "1") (pinfunction "1_1") (pintype "passive"))
    )
    (net (code "33") (name "unconnected-(J4-Pad2)") (class "Default")
      (node (ref "J4") (pin "2") (pinfunction "2_2") (pintype "passive"))
    )
    (net (code "34") (name "unconnected-(J4-Pad3)") (class "Default")
      (node (ref "J4") (pin "3") (pinfunction "3_3") (pintype "passive"))
    )
    (net (code "35") (name "unconnected-(J4-Pad4)") (class "Default")
      (node (ref "J4") (pin "4") (pinfunction "4_4") (pintype "passive"))
    )
    (net (code "36") (name "unconnected-(J4-Pad5)") (class "Default")
      (node (ref "J4") (pin "5") (pinfunction "5_5") (pintype "passive"))
    )
    (net (code "37") (name "unconnected-(J4-Pad6)") (class "Default")
      (node (ref "J4") (pin "6") (pinfunction "6_6") (pintype "passive"))
    )
    (net (code "38") (name "unconnected-(J4-Pad7)") (class "Default")
      (node (ref "J4") (pin "7") (pinfunction "7_7") (pintype "passive"))
    )
    (net (code "39") (name "unconnected-(S1-P-Pad3)") (class "Default")
      (node (ref "S1") (pin "3") (pinfunction "P_3") (pintype "passive"))
    )
    (net (code "40") (name "unconnected-(S2-P-Pad3)") (class "Default")
      (node (ref "S2") (pin "3") (pinfunction "P_3") (pintype "passive"))
    )
    (net (code "41") (name "unconnected-(S3-P-Pad3)") (class "Default")
      (node (ref "S3") (pin "3") (pinfunction "P_3") (pintype "passive"))
    )
    (net (code "42") (name "unconnected-(S4-P-Pad3)") (class "Default")
      (node (ref "S4") (pin "3") (pinfunction "P_3") (pintype "passive"))
    )
    (net (code "43") (name "unconnected-(S5-P-Pad3)") (class "Default")
      (node (ref "S5") (pin "3") (pinfunction "P_3") (pintype "passive"))
    )
    (net (code "44") (name "unconnected-(S6-P-Pad3)") (class "Default")
      (node (ref "S6") (pin "3") (pinfunction "P_3") (pintype "passive"))
    )
    (net (code "45") (name "unconnected-(S7-P-Pad3)") (class "Default")
      (node (ref "S7") (pin "3") (pinfunction "P_3") (pintype "passive"))
    )
    (net (code "46") (name "unconnected-(S8-P-Pad3)") (class "Default")
      (node (ref "S8") (pin "3") (pinfunction "P_3") (pintype "passive"))
    )
    (net (code "47") (name "unconnected-(S9-P-Pad3)") (class "Default")
      (node (ref "S9") (pin "3") (pinfunction "P_3") (pintype "passive"))
    )
    (net (code "48") (name "unconnected-(S10-P-Pad3)") (class "Default")
      (node (ref "S10") (pin "3") (pinfunction "P_3") (pintype "passive"))
    )
    (net (code "49") (name "unconnected-(S11-P-Pad3)") (class "Default")
      (node (ref "S11") (pin "3") (pinfunction "P_3") (pintype "passive"))
    )
    (net (code "50") (name "unconnected-(S12-P-Pad3)") (class "Default")
      (node (ref "S12") (pin "3") (pinfunction "P_3") (pintype "passive"))
    )
    (net (code "51") (name "unconnected-(S13-P-Pad3)") (class "Default")
      (node (ref "S13") (pin "3") (pinfunction "P_3") (pintype "passive"))
    )
    (net (code "52") (name "unconnected-(S14-P-Pad3)") (class "Default")
      (node (ref "S14") (pin "3") (pinfunction "P_3") (pintype "passive"))
    )
    (net (code "53") (name "unconnected-(S15-P-Pad3)") (class "Default")
      (node (ref "S15") (pin "3") (pinfunction "P_3") (pintype "passive"))
    )
    (net (code "54") (name "unconnected-(S16-P-Pad3)") (class "Default")
      (node (ref "S16") (pin "3") (pinfunction "P_3") (pintype "passive"))
    )
    (net (code "55") (name "unconnected-(S17-P-Pad3)") (class "Default")
      (node (ref "S17") (pin "3") (pinfunction "P_3") (pintype "passive"))
    )
    (net (code "56") (name "unconnected-(S18-P-Pad3)") (class "Default")
      (node (ref "S18") (pin "3") (pinfunction "P_3") (pintype "passive"))
    )
    (net (code "57") (name "unconnected-(S19-P-Pad3)") (class "Default")
      (node (ref "S19") (pin "3") (pinfunction "P_3") (pintype "passive"))
    )
    (net (code "58") (name "unconnected-(S20-P-Pad3)") (class "Default")
      (node (ref "S20") (pin "3") (pinfunction "P_3") (pintype "passive"))
    )
    (net (code "59") (name "unconnected-(S21-P-Pad3)") (class "Default")
      (node (ref "S21") (pin "3") (pinfunction "P_3") (pintype "passive"))
    )
    (net (code "60") (name "unconnected-(S22-P-Pad3)") (class "Default")
      (node (ref "S22") (pin "3") (pinfunction "P_3") (pintype "passive"))
    )
    (net (code "61") (name "unconnected-(S23-P-Pad3)") (class "Default")
      (node (ref "S23") (pin "3") (pinfunction "P_3") (pintype "passive"))
    )
    (net (code "62") (name "unconnected-(S24-P-Pad3)") (class "Default")
      (node (ref "S24") (pin "3") (pinfunction "P_3") (pintype "passive"))
    )
    (net (code "63") (name "unconnected-(S25-P-Pad3)") (class "Default")
      (node (ref "S25") (pin "3") (pinfunction "P_3") (pintype "passive"))
    )
    (net (code "64") (name "unconnected-(S26-P-Pad3)") (class "Default")
      (node (ref "S26") (pin "3") (pinfunction "P_3") (pintype "passive"))
    )
    (net (code "65") (name "unconnected-(S27-P-Pad3)") (class "Default")
      (node (ref "S27") (pin "3") (pinfunction "P_3") (pintype "passive"))
    )
    (net (code "66") (name "unconnected-(S28-P-Pad3)") (class "Default")
      (node (ref "S28") (pin "3") (pinfunction "P_3") (pintype "passive"))
    )
    (net (code "67") (name "unconnected-(S29-P-Pad3)") (class "Default")
      (node (ref "S29") (pin "3") (pinfunction "P_3") (pintype "passive"))
    )
    (net (code "68") (name "unconnected-(S30-P-Pad3)") (class "Default")
      (node (ref "S30") (pin "3") (pinfunction "P_3") (pintype "passive"))
    )
    (net (code "69") (name "unconnected-(S31-P-Pad3)") (class "Default")
      (node (ref "S31") (pin "3") (pinfunction "P_3") (pintype "passive"))
    )
    (net (code "70") (name "unconnected-(S32-P-Pad3)") (class "Default")
      (node (ref "S32") (pin "3") (pinfunction "P_3") (pintype "passive"))
    )
    (net (code "71") (name "unconnected-(S33-P-Pad3)") (class "Default")
      (node (ref "S33") (pin "3") (pinfunction "P_3") (pintype "passive"))
    )
    (net (code "72") (name "unconnected-(S34-P-Pad3)") (class "Default")
      (node (ref "S34") (pin "3") (pinfunction "P_3") (pintype "passive"))
    )
    (net (code "73") (name "unconnected-(S35-P-Pad3)") (class "Default")
      (node (ref "S35") (pin "3") (pinfunction "P_3") (pintype "passive"))
    )
    (net (code "74") (name "unconnected-(S36-P-Pad3)") (class "Default")
      (node (ref "S36") (pin "3") (pinfunction "P_3") (pintype "passive"))
    )
    (net (code "75") (name "unconnected-(S37-P-Pad3)") (class "Default")
      (node (ref "S37") (pin "3") (pinfunction "P_3") (pintype "passive"))
    )
    (net (code "76") (name "unconnected-(S38-P-Pad3)") (class "Default")
      (node (ref "S38") (pin "3") (pinfunction "P_3") (pintype "passive"))
    )
    (net (code "77") (name "unconnected-(S39-P-Pad3)") (class "Default")
      (node (ref "S39") (pin "3") (pinfunction "P_3") (pintype "passive"))
    )
    (net (code "78") (name "unconnected-(S40-P-Pad3)") (class "Default")
      (node (ref "S40") (pin "3") (pinfunction "P_3") (pintype "passive"))
    )
    (net (code "79") (name "unconnected-(S41-P-Pad3)") (class "Default")
      (node (ref "S41") (pin "3") (pinfunction "P_3") (pintype "passive"))
    )
    (net (code "80") (name "unconnected-(S42-P-Pad3)") (class "Default")
      (node (ref "S42") (pin "3") (pinfunction "P_3") (pintype "passive"))
    )
    (net (code "81") (name "unconnected-(S43-P-Pad3)") (class "Default")
      (node (ref "S43") (pin "3") (pinfunction "P_3") (pintype "passive"))
    )
    (net (code "82") (name "unconnected-(S44-P-Pad3)") (class "Default")
      (node (ref "S44") (pin "3") (pinfunction "P_3") (pintype "passive"))
    )
    (net (code "83") (name "unconnected-(S45-P-Pad3)") (class "Default")
      (node (ref "S45") (pin "3") (pinfunction "P_3") (pintype "passive"))
    )
    (net (code "84") (name "unconnected-(S46-P-Pad3)") (class "Default")
      (node (ref "S46") (pin "3") (pinfunction "P_3") (pintype "passive"))
    )
    (net (code "85") (name "unconnected-(S47-P-Pad3)") (class "Default")
      (node (ref "S47") (pin "3") (pinfunction "P_3") (pintype "passive"))
    )
    (net (code "86") (name "unconnected-(S48-P-Pad3)") (class "Default")
      (node (ref "S48") (pin "3") (pinfunction "P_3") (pintype "passive"))
    )
    (net (code "87") (name "unconnected-(S49-P-Pad3)") (class "Default")
      (node (ref "S49") (pin "3") (pinfunction "P_3") (pintype "passive"))
    )
    (net (code "88") (name "unconnected-(S50-P-Pad3)") (class "Default")
      (node (ref "S50") (pin "3") (pinfunction "P_3") (pintype "passive"))
    )
    (net (code "89") (name "unconnected-(S51-P-Pad3)") (class "Default")
      (node (ref "S51") (pin "3") (pinfunction "P_3") (pintype "passive"))
    )
    (net (code "90") (name "unconnected-(S52-P-Pad3)") (class "Default")
      (node (ref "S52") (pin "3") (pinfunction "P_3") (pintype "passive"))
    )
    (net (code "91") (name "unconnected-(S53-P-Pad3)") (class "Default")
      (node (ref "S53") (pin "3") (pinfunction "P_3") (pintype "passive"))
    )
    (net (code "92") (name "unconnected-(S54-P-Pad3)") (class "Default")
      (node (ref "S54") (pin "3") (pinfunction "P_3") (pintype "passive"))
    )
    (net (code "93") (name "unconnected-(S55-P-Pad3)") (class "Default")
      (node (ref "S55") (pin "3") (pinfunction "P_3") (pintype "passive"))
    )
    (net (code "94") (name "unconnected-(S56-P-Pad3)") (class "Default")
      (node (ref "S56") (pin "3") (pinfunction "P_3") (pintype "passive"))
    )
    (net (code "95") (name "unconnected-(S57-P-Pad3)") (class "Default")
      (node (ref "S57") (pin "3") (pinfunction "P_3") (pintype "passive"))
    )
    (net (code "96") (name "unconnected-(S58-P-Pad3)") (class "Default")
      (node (ref "S58") (pin "3") (pinfunction "P_3") (pintype "passive"))
    )
    (net (code "97") (name "unconnected-(S59-P-Pad3)") (class "Default")
      (node (ref "S59") (pin "3") (pinfunction "P_3") (pintype "passive"))
    )
    (net (code "98") (name "unconnected-(S60-P-Pad3)") (class "Default")
      (node (ref "S60") (pin "3") (pinfunction "P_3") (pintype "passive"))
    )
  )
)
